# dedo_prog_r1_2.net
KiCad netlist of a schematic drawn in EAGLE
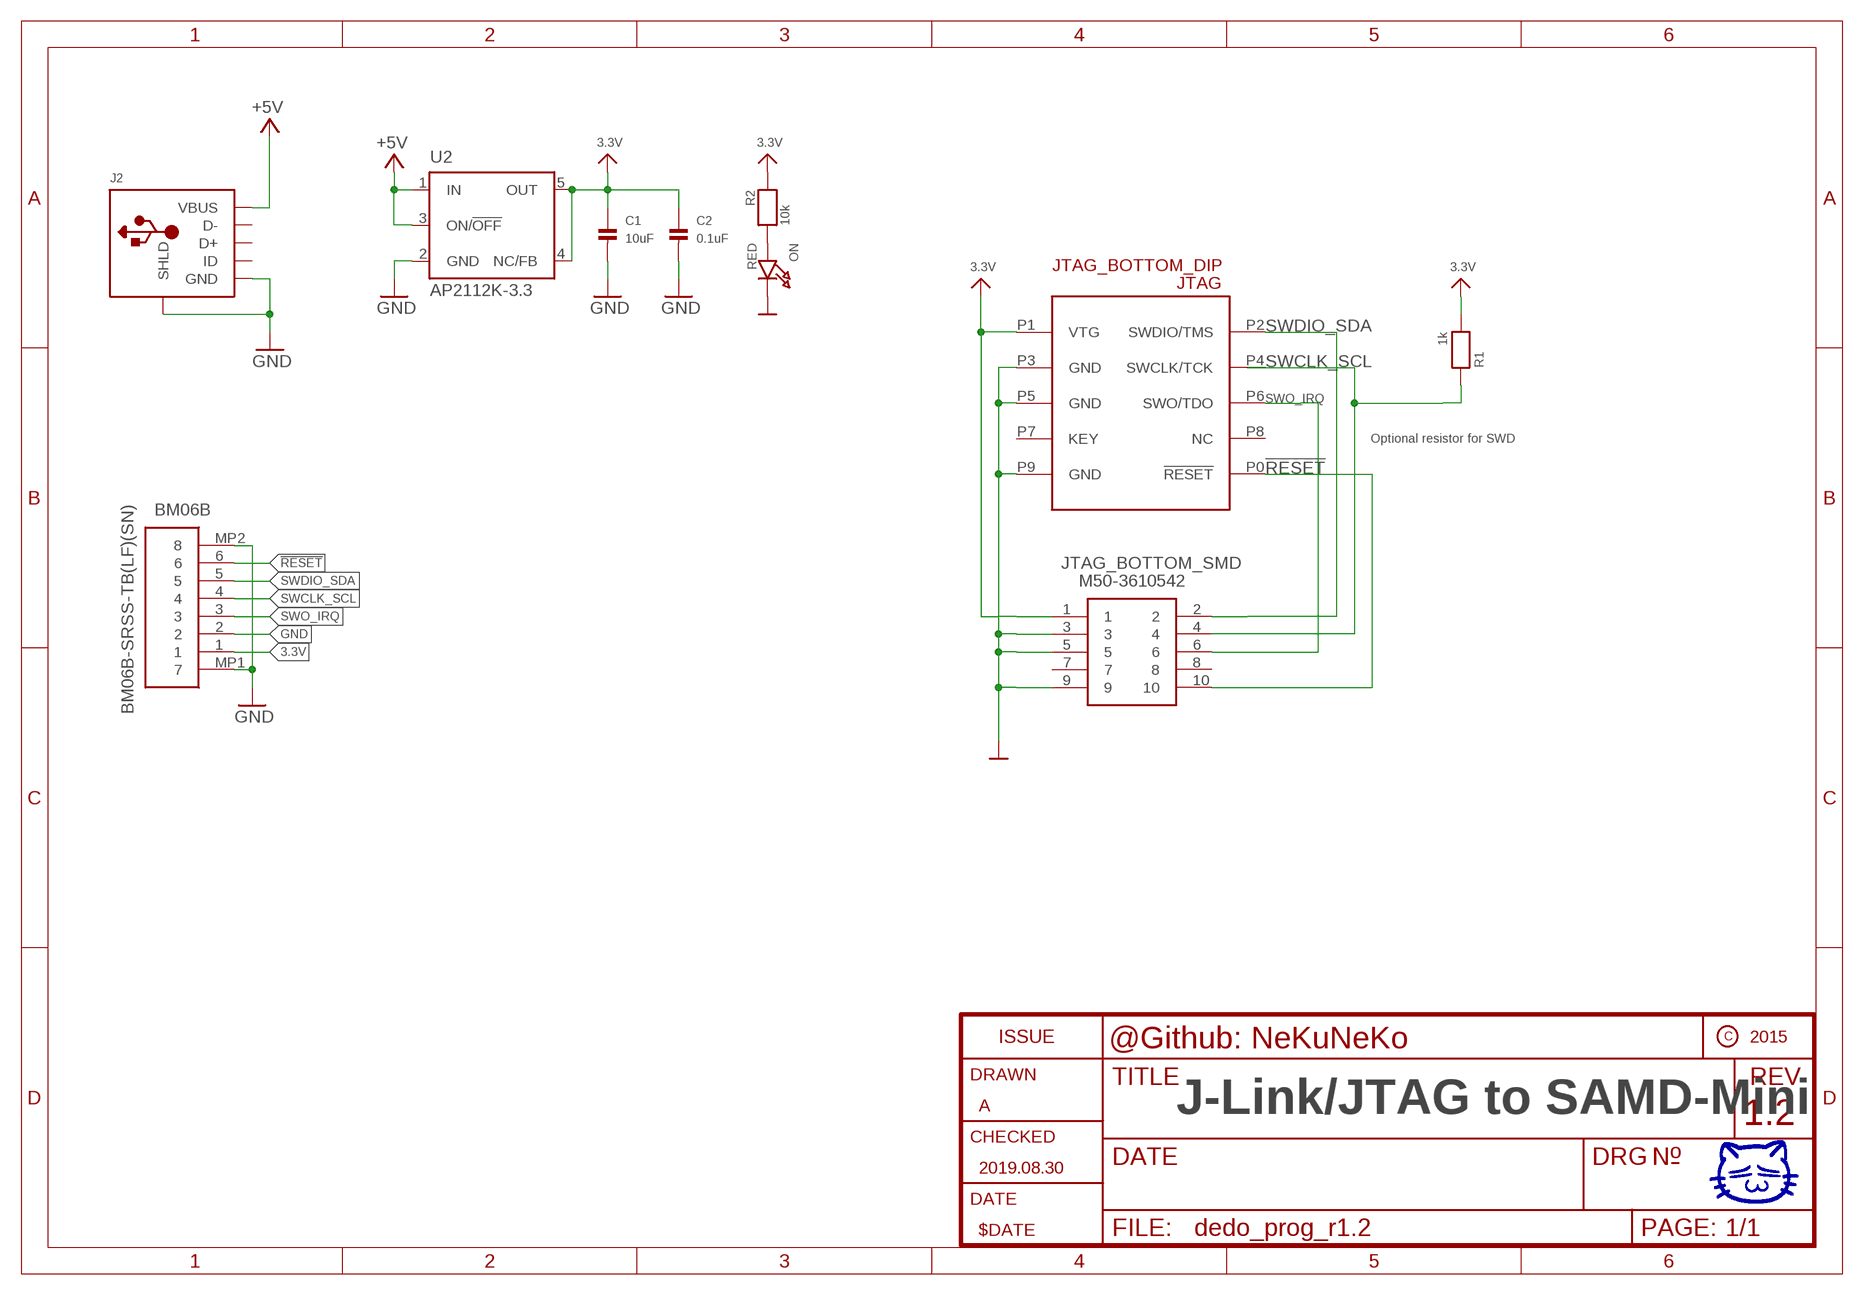
[diagram p0: schematic, sheet 1]

(export (version "E")
  (design (tool "Eeschema 10.0.6"))
  (components
    (comp (ref "BM06B")
      (value "BM06B-SRSS-TB(LF)(SN)")
      (footprint "eagle-import:BM06BSRSSTBLFSN")
      (fields (field (name "RS_PART_NUMBER") "5468782"))
      (libsource (lib "eagle-import") (part "BM06B-SRSS-TB(LF)(SN)"))
    )
    (comp (ref "C1")
      (value "10uF")
      (footprint "eagle-import:_0402")
      (libsource (lib "eagle-import") (part "CAP_CERAMIC_0402"))
    )
    (comp (ref "C2")
      (value "0.1uF")
      (footprint "eagle-import:_0402")
      (libsource (lib "eagle-import") (part "CAP_CERAMIC_0402"))
    )
    (comp (ref "J2")
      (value "FLAT_MICROUSB_ALIEXPRESS_TYPE_4")
      (footprint "eagle-import:USB_TYPE_4_105164-0001")
      (libsource (lib "eagle-import") (part "FLAT_MICROUSB_ALIEXPRESS_TYPE_4"))
    )
    (comp (ref "JTAG_BOTTOM_DIP")
      (value "JTAGICE3-CONNECTOR50MIL-THT")
      (footprint "eagle-import:JTAGICE3-50MIL")
      (libsource (lib "eagle-import") (part "JTAGICE3-CONNECTOR50MIL-THT"))
    )
    (comp (ref "JTAG_BOTTOM_SMD")
      (value "M50-3610542")
      (footprint "eagle-import:M503610542")
      (fields (field (name "MOUSER_PART_NUMBER") "855-M50-3610542"))
      (libsource (lib "eagle-import") (part "M50-3610542"))
    )
    (comp (ref "ON")
      (value "RED")
      (footprint "eagle-import:CHIPLED_0603")
      (libsource (lib "eagle-import") (part "LED0603"))
    )
    (comp (ref "R1")
      (value "1k")
      (footprint "eagle-import:_0402")
      (libsource (lib "eagle-import") (part "RESISTOR_0402"))
    )
    (comp (ref "R2")
      (value "10k")
      (footprint "eagle-import:_0402")
      (libsource (lib "eagle-import") (part "RESISTOR_0402"))
    )
    (comp (ref "U2")
      (value "AP2112K-3.3")
      (footprint "eagle-import:SOT23-DBV")
      (libsource (lib "eagle-import") (part "LP2985-XXDBVR33"))
    )
  )
  (nets
    (net (code "1") (name "+5V") (class "Default")
      (node (ref "J2") (pin "P$5") (pinfunction "VBUS_P$5") (pintype "power_in"))
      (node (ref "U2") (pin "1") (pinfunction "IN_1") (pintype "input"))
      (node (ref "U2") (pin "3") (pinfunction "ON/~{OFF}_3") (pintype "input"))
    )
    (net (code "2") (name "/~{RESET}") (class "Default")
      (node (ref "BM06B") (pin "6") (pinfunction "6_6") (pintype "bidirectional"))
      (node (ref "JTAG_BOTTOM_DIP") (pin "P0") (pinfunction "~{RESET}_P0") (pintype "bidirectional"))
      (node (ref "JTAG_BOTTOM_SMD") (pin "10") (pinfunction "10_10") (pintype "bidirectional"))
    )
    (net (code "3") (name "3.3V") (class "Default")
      (node (ref "BM06B") (pin "1") (pinfunction "1_1") (pintype "bidirectional"))
      (node (ref "C1") (pin "1") (pinfunction "P$1_1") (pintype "passive"))
      (node (ref "C2") (pin "1") (pinfunction "P$1_1") (pintype "passive"))
      (node (ref "JTAG_BOTTOM_DIP") (pin "P1") (pinfunction "VTG_P1") (pintype "bidirectional"))
      (node (ref "JTAG_BOTTOM_SMD") (pin "1") (pinfunction "1_1") (pintype "bidirectional"))
      (node (ref "R1") (pin "2") (pinfunction "2_2") (pintype "passive"))
      (node (ref "R2") (pin "2") (pinfunction "2_2") (pintype "passive"))
      (node (ref "U2") (pin "4") (pinfunction "NC/FB_4") (pintype "passive"))
      (node (ref "U2") (pin "5") (pinfunction "OUT_5") (pintype "passive"))
    )
    (net (code "4") (name "GND") (class "Default")
      (node (ref "BM06B") (pin "2") (pinfunction "2_2") (pintype "bidirectional"))
      (node (ref "BM06B") (pin "MP1") (pinfunction "7_MP1") (pintype "bidirectional"))
      (node (ref "BM06B") (pin "MP2") (pinfunction "8_MP2") (pintype "bidirectional"))
      (node (ref "C1") (pin "2") (pinfunction "P$2_2") (pintype "passive"))
      (node (ref "C2") (pin "2") (pinfunction "P$2_2") (pintype "passive"))
      (node (ref "J2") (pin "P$1") (pinfunction "GND_P$1") (pintype "power_in"))
      (node (ref "J2") (pin "P$8") (pinfunction "SHLD_P$8") (pintype "power_in"))
      (node (ref "J2") (pin "P$9") (pinfunction "SHLD_P$9") (pintype "power_in"))
      (node (ref "JTAG_BOTTOM_DIP") (pin "P3") (pinfunction "GND_P3") (pintype "bidirectional"))
      (node (ref "JTAG_BOTTOM_DIP") (pin "P5") (pinfunction "GND_P5") (pintype "bidirectional"))
      (node (ref "JTAG_BOTTOM_DIP") (pin "P9") (pinfunction "GND_P9") (pintype "bidirectional"))
      (node (ref "JTAG_BOTTOM_SMD") (pin "3") (pinfunction "3_3") (pintype "bidirectional"))
      (node (ref "JTAG_BOTTOM_SMD") (pin "5") (pinfunction "5_5") (pintype "bidirectional"))
      (node (ref "JTAG_BOTTOM_SMD") (pin "9") (pinfunction "9_9") (pintype "bidirectional"))
      (node (ref "ON") (pin "C") (pinfunction "C_C") (pintype "passive"))
      (node (ref "U2") (pin "2") (pinfunction "GND_2") (pintype "power_in"))
    )
    (net (code "5") (name "Net-(ON-PadA)") (class "Default")
      (node (ref "ON") (pin "A") (pinfunction "A_A") (pintype "passive"))
      (node (ref "R2") (pin "1") (pinfunction "1_1") (pintype "passive"))
    )
    (net (code "6") (name "SWCLK_SCL") (class "Default")
      (node (ref "BM06B") (pin "4") (pinfunction "4_4") (pintype "bidirectional"))
      (node (ref "JTAG_BOTTOM_DIP") (pin "P4") (pinfunction "SWCLK/TCK_P4") (pintype "bidirectional"))
      (node (ref "JTAG_BOTTOM_SMD") (pin "4") (pinfunction "4_4") (pintype "bidirectional"))
      (node (ref "R1") (pin "1") (pinfunction "1_1") (pintype "passive"))
    )
    (net (code "7") (name "SWDIO_SDA") (class "Default")
      (node (ref "BM06B") (pin "5") (pinfunction "5_5") (pintype "bidirectional"))
      (node (ref "JTAG_BOTTOM_DIP") (pin "P2") (pinfunction "SWDIO/TMS_P2") (pintype "bidirectional"))
      (node (ref "JTAG_BOTTOM_SMD") (pin "2") (pinfunction "2_2") (pintype "bidirectional"))
    )
    (net (code "8") (name "SWO_IRQ") (class "Default")
      (node (ref "BM06B") (pin "3") (pinfunction "3_3") (pintype "bidirectional"))
      (node (ref "JTAG_BOTTOM_DIP") (pin "P6") (pinfunction "SWO/TDO_P6") (pintype "bidirectional"))
      (node (ref "JTAG_BOTTOM_SMD") (pin "6") (pinfunction "6_6") (pintype "bidirectional"))
    )
    (net (code "9") (name "unconnected-(J2-D+-PadP$3)") (class "Default")
      (node (ref "J2") (pin "P$3") (pinfunction "D+_P$3") (pintype "bidirectional"))
    )
    (net (code "10") (name "unconnected-(J2-D--PadP$4)") (class "Default")
      (node (ref "J2") (pin "P$4") (pinfunction "D-_P$4") (pintype "bidirectional"))
    )
    (net (code "11") (name "unconnected-(J2-ID-PadP$2)") (class "Default")
      (node (ref "J2") (pin "P$2") (pinfunction "ID_P$2") (pintype "bidirectional"))
    )
    (net (code "12") (name "unconnected-(JTAG_BOTTOM_DIP-KEY-PadP7)") (class "Default")
      (node (ref "JTAG_BOTTOM_DIP") (pin "P7") (pinfunction "KEY_P7") (pintype "bidirectional"))
    )
    (net (code "13") (name "unconnected-(JTAG_BOTTOM_DIP-NC-PadP8)") (class "Default")
      (node (ref "JTAG_BOTTOM_DIP") (pin "P8") (pinfunction "NC_P8") (pintype "bidirectional"))
    )
    (net (code "14") (name "unconnected-(JTAG_BOTTOM_SMD-Pad7)") (class "Default")
      (node (ref "JTAG_BOTTOM_SMD") (pin "7") (pinfunction "7_7") (pintype "bidirectional"))
    )
    (net (code "15") (name "unconnected-(JTAG_BOTTOM_SMD-Pad8)") (class "Default")
      (node (ref "JTAG_BOTTOM_SMD") (pin "8") (pinfunction "8_8") (pintype "bidirectional"))
    )
  )
)
